# tlv117_5_3_3.net
KiCad netlist of a schematic drawn in Altium Designer
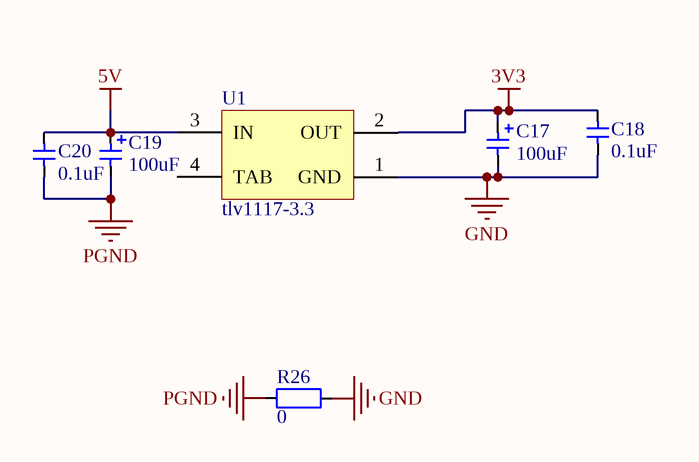
[diagram p0: tlv117_5_3.3.SchDoc]

(export (version "E")
  (design (tool "Eeschema 10.0.6"))
  (components
    (comp (ref "C17")
      (value "100uF")
      (footprint "CAP-TAN-6032/CAPC")
      (description "Capacitor")
      (fields (field (name "Comment") "Cap_Tan_0805"))
      (libsource (lib "Integrated_Library") (part "Cap_Tan_0805"))
    )
    (comp (ref "C18")
      (value "0.1uF")
      (footprint "CAP_0603")
      (description "Capacitor")
      (fields (field (name "Comment") "Cap_0603"))
      (libsource (lib "Integrated_Library") (part "Cap_0603"))
    )
    (comp (ref "C19")
      (value "100uF")
      (footprint "CAP-TAN-6032/CAPC")
      (description "Capacitor")
      (fields (field (name "Comment") "Cap_Tan_0805"))
      (libsource (lib "Integrated_Library") (part "Cap_Tan_0805"))
    )
    (comp (ref "C20")
      (value "0.1uF")
      (footprint "CAP_0603")
      (description "Capacitor")
      (fields (field (name "Comment") "Cap_0603"))
      (libsource (lib "Integrated_Library") (part "Cap_0603"))
    )
    (comp (ref "R26")
      (value "0")
      (footprint "RES_0603")
      (description "Resistor")
      (fields (field (name "Comment") "Res_0603"))
      (libsource (lib "Integrated_Library") (part "Res_0603"))
    )
    (comp (ref "U1")
      (value "tlv1117-3.3")
      (footprint "SOT223-3")
      (description "800mA Low-Dropout Linear Regulator")
      (fields
        (field (name "PARTNUMBER") "LM1117IMP-5.0")
        (field (name "MANUFACTURER") "National Semiconductor")
        (field (name "PUBLISHER") "Altium Limited")
      )
      (libsource (lib "K60-mainboard-v3.1") (part "LM1117IMP-5.0"))
    )
  )
  (nets
    (net (code "1") (name "3V3") (class "Default")
      (node (ref "C17") (pin "1") (pinfunction "1_1") (pintype "passive"))
      (node (ref "C18") (pin "2") (pinfunction "2_2") (pintype "passive"))
      (node (ref "U1") (pin "2") (pinfunction "OUT_2") (pintype "power_in"))
    )
    (net (code "2") (name "5V") (class "Default")
      (node (ref "C19") (pin "1") (pinfunction "1_1") (pintype "passive"))
      (node (ref "C20") (pin "2") (pinfunction "2_2") (pintype "passive"))
      (node (ref "U1") (pin "3") (pinfunction "IN_3") (pintype "power_in"))
    )
    (net (code "3") (name "GND") (class "Default")
      (node (ref "C17") (pin "2") (pinfunction "2_2") (pintype "passive"))
      (node (ref "C18") (pin "1") (pinfunction "1_1") (pintype "passive"))
      (node (ref "R26") (pin "2") (pinfunction "2_2") (pintype "passive"))
      (node (ref "U1") (pin "1") (pinfunction "GND_1") (pintype "power_in"))
    )
    (net (code "4") (name "PGND") (class "Default")
      (node (ref "C19") (pin "2") (pinfunction "2_2") (pintype "passive"))
      (node (ref "C20") (pin "1") (pinfunction "1_1") (pintype "passive"))
      (node (ref "R26") (pin "1") (pinfunction "1_1") (pintype "passive"))
    )
    (net (code "5") (name "unconnected-(U1-TAB-Pad4)") (class "Default")
      (node (ref "U1") (pin "4") (pinfunction "TAB_4") (pintype "power_in"))
    )
  )
)
